# IOTLoRaSmartGreenhouseNode.net
KiCad netlist of a schematic drawn in Altium Designer
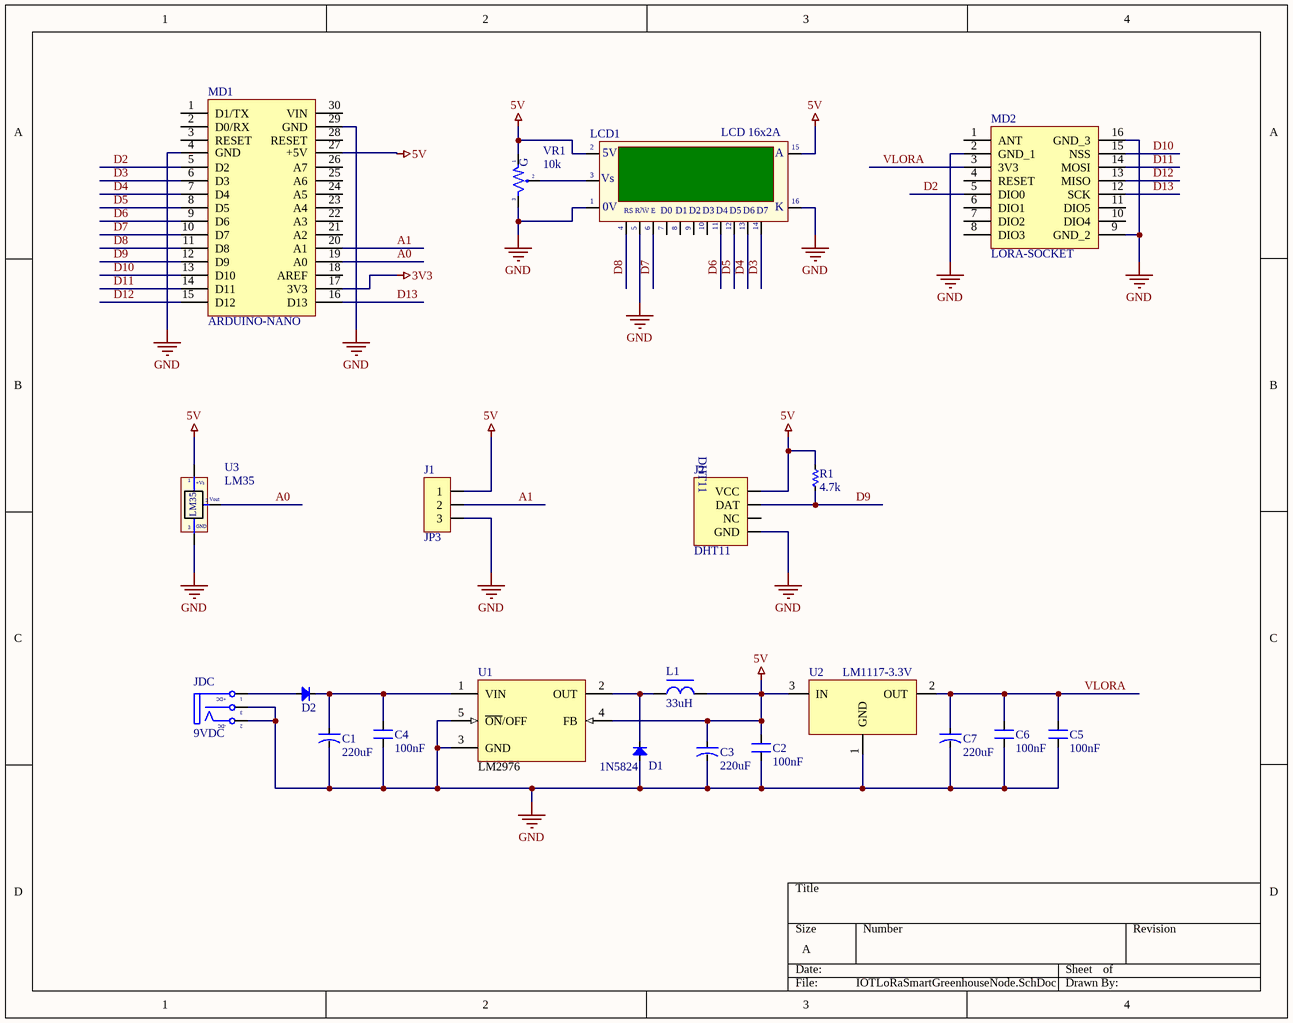
[diagram p0: IOTLoRaSmartGreenhouseNode.SchDoc]

(export (version "E")
  (design (tool "Eeschema 10.0.6"))
  (components
    (comp (ref "C1")
      (value "220uF")
      (footprint "CA-ALU-8")
      (description "Capacitor (Semiconductor SIM Model)")
      (fields (field (name "PUBLISHER") "Altium Limited"))
      (libsource (lib "LIBRARY") (part "CN-ALU-DIP"))
    )
    (comp (ref "C2") (value "100nF") (footprint "CN1.5") (libsource (lib "LIBRARY") (part "CN")))
    (comp (ref "C3")
      (value "220uF")
      (footprint "CA-ALU-8")
      (description "Capacitor (Semiconductor SIM Model)")
      (fields (field (name "PUBLISHER") "Altium Limited"))
      (libsource (lib "LIBRARY") (part "CN-ALU-DIP"))
    )
    (comp (ref "C4") (value "100nF") (footprint "CN1.5") (libsource (lib "LIBRARY") (part "CN")))
    (comp (ref "C5") (value "100nF") (footprint "CN1.5") (libsource (lib "LIBRARY") (part "CN")))
    (comp (ref "C6") (value "100nF") (footprint "CN1.5") (libsource (lib "LIBRARY") (part "CN")))
    (comp (ref "C7")
      (value "220uF")
      (footprint "CA-ALU-8")
      (description "Capacitor (Semiconductor SIM Model)")
      (fields (field (name "PUBLISHER") "Altium Limited"))
      (libsource (lib "LIBRARY") (part "CN-ALU-DIP"))
    )
    (comp (ref "D1")
      (value "1N5824")
      (footprint "DIO-5A")
      (description "Default Diode")
      (fields (field (name "PUBLISHER") "Altium Limited"))
      (libsource (lib "LIBRARY") (part "Diode"))
    )
    (comp (ref "D2")
      (value "Diode")
      (footprint "DIO-3A")
      (description "Default Diode")
      (fields (field (name "PUBLISHER") "Altium Limited"))
      (libsource (lib "LIBRARY") (part "Diode"))
    )
    (comp (ref "J1")
      (value "JP3")
      (footprint "JP3-D1C")
      (description "WR-PHD 2.54 mm Angled Socket Header")
      (fields
        (field (name "MANUFACTURER") "Würth Elektronik eiSos GmbH")
        (field (name "PARTNO") "613003143121")
        (field (name "CREATED BY") "Karrer Zheng")
      )
      (libsource (lib "LIBRARY") (part "JP3"))
    )
    (comp (ref "J2")
      (value "DHT11")
      (footprint "JP4-C1T")
      (fields
        (field (name "MANUFACTURER") "Würth Elektronik eiSos GmbH")
        (field (name "PARTNO") "613004143121")
        (field (name "CREATED BY") "Karrer Zheng")
      )
      (libsource (lib "LIBRARY") (part "DHT11"))
    )
    (comp (ref "JDC")
      (value "9VDC")
      (footprint "DC0")
      (description "Jac DC input")
      (libsource (lib "LIBRARY") (part "DCIN"))
    )
    (comp (ref "L1")
      (value "33uH")
      (footprint "L-DIP-M-10")
      (description "Inductor")
      (libsource (lib "LIBRARY") (part "L-DIP-1"))
    )
    (comp (ref "LCD1")
      (value "LCD 16x2A")
      (footprint "LCD16X2N")
      (description "LCD dipslay 16 char, 2 line")
      (libsource (lib "LIBRARY") (part "LCD16x2A"))
    )
    (comp (ref "MD1")
      (value "ARDUINO-NANO")
      (footprint "ARDUINO-NANO")
      (description "KIT Arduino Nano")
      (libsource (lib "phatvu1294_Lib") (part "ARDUINO-NANO"))
    )
    (comp (ref "MD2")
      (value "LORA-SOCKET")
      (footprint "LORA-SOCKET")
      (description "Socket LoRa RA01 va RA02")
      (libsource (lib "User") (part "LORA-SOCKET"))
    )
    (comp (ref "R1")
      (value "4.7k")
      (footprint "RES-1/4W")
      (description "Res")
      (fields
        (field (name "MANUFACTURER") "Generic Components")
        (field (name "PUBLISHER") "Altium Hobart Technology Centre")
      )
      (libsource (lib "LIBRARY") (part "Res"))
    )
    (comp (ref "U1") (value "LM2976") (footprint "TO263") (libsource (lib "LIBRARY") (part "LM2596")))
    (comp (ref "U2")
      (value "LM1117-3.3V")
      (footprint "SOT223")
      (description "800mA Low-Dropout Linear Regulator")
      (fields (field (name "CREATOR") "Nguyen Ba Bien"))
      (libsource (lib "LIBRARY") (part "LM1117"))
    )
    (comp (ref "U3")
      (value "LM35")
      (footprint "TO92-123")
      (description "Teminal")
      (libsource (lib "LIBRARY") (part "LM35"))
    )
    (comp (ref "VR1")
      (value "10k")
      (footprint "VR-S2")
      (description "Var Resistor")
      (libsource (lib "LIBRARY") (part "VR-S"))
    )
  )
  (nets
    (net (code "1") (name "/A0") (class "Default")
      (node (ref "MD1") (pin "19") (pinfunction "A0_19") (pintype "passive"))
      (node (ref "U3") (pin "2") (pinfunction "Vout_2") (pintype "passive"))
    )
    (net (code "2") (name "/A1") (class "Default")
      (node (ref "J1") (pin "2") (pinfunction "2_2") (pintype "passive"))
      (node (ref "MD1") (pin "20") (pinfunction "A1_20") (pintype "passive"))
    )
    (net (code "3") (name "/D2") (class "Default")
      (node (ref "MD1") (pin "5") (pinfunction "D2_5") (pintype "passive"))
      (node (ref "MD2") (pin "5") (pinfunction "DIO0_5") (pintype "passive"))
    )
    (net (code "4") (name "/D3") (class "Default")
      (node (ref "LCD1") (pin "14") (pinfunction "D7_14") (pintype "passive"))
      (node (ref "MD1") (pin "6") (pinfunction "D3_6") (pintype "passive"))
    )
    (net (code "5") (name "/D4") (class "Default")
      (node (ref "LCD1") (pin "13") (pinfunction "D6_13") (pintype "passive"))
      (node (ref "MD1") (pin "7") (pinfunction "D4_7") (pintype "passive"))
    )
    (net (code "6") (name "/D5") (class "Default")
      (node (ref "LCD1") (pin "12") (pinfunction "D5_12") (pintype "passive"))
      (node (ref "MD1") (pin "8") (pinfunction "D5_8") (pintype "passive"))
    )
    (net (code "7") (name "/D6") (class "Default")
      (node (ref "LCD1") (pin "11") (pinfunction "D4_11") (pintype "passive"))
      (node (ref "MD1") (pin "9") (pinfunction "D6_9") (pintype "passive"))
    )
    (net (code "8") (name "/D7") (class "Default")
      (node (ref "LCD1") (pin "6") (pinfunction "~{EN}_6") (pintype "passive"))
      (node (ref "MD1") (pin "10") (pinfunction "D7_10") (pintype "passive"))
    )
    (net (code "9") (name "/D8") (class "Default")
      (node (ref "LCD1") (pin "4") (pinfunction "RS_4") (pintype "passive"))
      (node (ref "MD1") (pin "11") (pinfunction "D8_11") (pintype "passive"))
    )
    (net (code "10") (name "/D9") (class "Default")
      (node (ref "J2") (pin "2") (pinfunction "DAT_2") (pintype "passive"))
      (node (ref "MD1") (pin "12") (pinfunction "D9_12") (pintype "passive"))
      (node (ref "R1") (pin "2") (pinfunction "2_2") (pintype "passive"))
    )
    (net (code "11") (name "/D10") (class "Default")
      (node (ref "MD1") (pin "13") (pinfunction "D10_13") (pintype "passive"))
      (node (ref "MD2") (pin "15") (pinfunction "NSS_15") (pintype "passive"))
    )
    (net (code "12") (name "/D11") (class "Default")
      (node (ref "MD1") (pin "14") (pinfunction "D11_14") (pintype "passive"))
      (node (ref "MD2") (pin "14") (pinfunction "MOSI_14") (pintype "passive"))
    )
    (net (code "13") (name "/D12") (class "Default")
      (node (ref "MD1") (pin "15") (pinfunction "D12_15") (pintype "passive"))
      (node (ref "MD2") (pin "13") (pinfunction "MISO_13") (pintype "passive"))
    )
    (net (code "14") (name "/D13") (class "Default")
      (node (ref "MD1") (pin "16") (pinfunction "D13_16") (pintype "passive"))
      (node (ref "MD2") (pin "12") (pinfunction "SCK_12") (pintype "passive"))
    )
    (net (code "15") (name "/VLORA") (class "Default")
      (node (ref "C5") (pin "1") (pinfunction "1_1") (pintype "passive"))
      (node (ref "C6") (pin "1") (pinfunction "1_1") (pintype "passive"))
      (node (ref "C7") (pin "1") (pinfunction "1_1") (pintype "passive"))
      (node (ref "MD2") (pin "3") (pinfunction "3V3_3") (pintype "passive"))
      (node (ref "U2") (pin "2") (pinfunction "OUT_2") (pintype "passive"))
    )
    (net (code "16") (name "3V3") (class "Default")
      (node (ref "MD1") (pin "17") (pinfunction "3V3_17") (pintype "passive"))
    )
    (net (code "17") (name "5V") (class "Default")
      (node (ref "C2") (pin "1") (pinfunction "1_1") (pintype "passive"))
      (node (ref "C3") (pin "1") (pinfunction "1_1") (pintype "passive"))
      (node (ref "J1") (pin "1") (pinfunction "1_1") (pintype "passive"))
      (node (ref "J2") (pin "1") (pinfunction "VCC_1") (pintype "passive"))
      (node (ref "L1") (pin "2") (pinfunction "2_2") (pintype "passive"))
      (node (ref "LCD1") (pin "15") (pinfunction "A_15") (pintype "passive"))
      (node (ref "LCD1") (pin "2") (pinfunction "VDD_2") (pintype "passive"))
      (node (ref "MD1") (pin "27") (pinfunction "+5V_27") (pintype "passive"))
      (node (ref "R1") (pin "1") (pinfunction "1_1") (pintype "passive"))
      (node (ref "U1") (pin "4") (pinfunction "FB_4") (pintype "input"))
      (node (ref "U2") (pin "3") (pinfunction "IN_3") (pintype "passive"))
      (node (ref "U3") (pin "1") (pinfunction "+Vs_1") (pintype "passive"))
      (node (ref "VR1") (pin "1") (pinfunction "1_1") (pintype "passive"))
    )
    (net (code "18") (name "GND") (class "Default")
      (node (ref "C1") (pin "2") (pinfunction "2_2") (pintype "passive"))
      (node (ref "C2") (pin "2") (pinfunction "2_2") (pintype "passive"))
      (node (ref "C3") (pin "2") (pinfunction "2_2") (pintype "passive"))
      (node (ref "C4") (pin "2") (pinfunction "2_2") (pintype "passive"))
      (node (ref "C5") (pin "2") (pinfunction "2_2") (pintype "passive"))
      (node (ref "C6") (pin "2") (pinfunction "2_2") (pintype "passive"))
      (node (ref "C7") (pin "2") (pinfunction "2_2") (pintype "passive"))
      (node (ref "D1") (pin "1") (pinfunction "A_1") (pintype "passive"))
      (node (ref "J1") (pin "3") (pinfunction "3_3") (pintype "passive"))
      (node (ref "J2") (pin "4") (pinfunction "GND_4") (pintype "passive"))
      (node (ref "JDC") (pin "2") (pinfunction "TN_2") (pintype "passive"))
      (node (ref "JDC") (pin "3") (pinfunction "S_3") (pintype "power_in"))
      (node (ref "LCD1") (pin "1") (pinfunction "GND_1") (pintype "passive"))
      (node (ref "LCD1") (pin "16") (pinfunction "K_16") (pintype "passive"))
      (node (ref "LCD1") (pin "5") (pinfunction "R/~{W}_5") (pintype "passive"))
      (node (ref "MD1") (pin "29") (pinfunction "GND_29") (pintype "passive"))
      (node (ref "MD1") (pin "4") (pinfunction "GND_4") (pintype "passive"))
      (node (ref "MD2") (pin "16") (pinfunction "GND_3_16") (pintype "passive"))
      (node (ref "MD2") (pin "2") (pinfunction "GND_1_2") (pintype "passive"))
      (node (ref "MD2") (pin "9") (pinfunction "GND_2_9") (pintype "passive"))
      (node (ref "U1") (pin "3") (pinfunction "GND_3") (pintype "power_in"))
      (node (ref "U1") (pin "5") (pinfunction "~{ON}/OFF_5") (pintype "input"))
      (node (ref "U2") (pin "1") (pinfunction "GND_1") (pintype "passive"))
      (node (ref "U3") (pin "3") (pinfunction "-_3") (pintype "passive"))
      (node (ref "VR1") (pin "3") (pinfunction "3_3") (pintype "passive"))
    )
    (net (code "19") (name "Net-(D1-K)") (class "Default")
      (node (ref "D1") (pin "2") (pinfunction "K_2") (pintype "passive"))
      (node (ref "L1") (pin "1") (pinfunction "1_1") (pintype "passive"))
      (node (ref "U1") (pin "2") (pinfunction "OUT_2") (pintype "power_in"))
    )
    (net (code "20") (name "Net-(D2-A)") (class "Default")
      (node (ref "D2") (pin "1") (pinfunction "A_1") (pintype "passive"))
      (node (ref "JDC") (pin "1") (pinfunction "T_1") (pintype "passive"))
    )
    (net (code "21") (name "Net-(D2-K)") (class "Default")
      (node (ref "C1") (pin "1") (pinfunction "1_1") (pintype "passive"))
      (node (ref "C4") (pin "1") (pinfunction "1_1") (pintype "passive"))
      (node (ref "D2") (pin "2") (pinfunction "K_2") (pintype "passive"))
      (node (ref "U1") (pin "1") (pinfunction "VIN_1") (pintype "power_in"))
    )
    (net (code "22") (name "Net-(LCD1-VEE)") (class "Default")
      (node (ref "LCD1") (pin "3") (pinfunction "VEE_3") (pintype "passive"))
      (node (ref "VR1") (pin "2") (pinfunction "2_2") (pintype "passive"))
    )
    (net (code "23") (name "unconnected-(J2-NC-Pad3)") (class "Default")
      (node (ref "J2") (pin "3") (pinfunction "NC_3") (pintype "passive"))
    )
    (net (code "24") (name "unconnected-(LCD1-D0-Pad7)") (class "Default")
      (node (ref "LCD1") (pin "7") (pinfunction "D0_7") (pintype "passive"))
    )
    (net (code "25") (name "unconnected-(LCD1-D1-Pad8)") (class "Default")
      (node (ref "LCD1") (pin "8") (pinfunction "D1_8") (pintype "passive"))
    )
    (net (code "26") (name "unconnected-(LCD1-D2-Pad9)") (class "Default")
      (node (ref "LCD1") (pin "9") (pinfunction "D2_9") (pintype "passive"))
    )
    (net (code "27") (name "unconnected-(LCD1-D3-Pad10)") (class "Default")
      (node (ref "LCD1") (pin "10") (pinfunction "D3_10") (pintype "passive"))
    )
    (net (code "28") (name "unconnected-(MD1-A2-Pad21)") (class "Default")
      (node (ref "MD1") (pin "21") (pinfunction "A2_21") (pintype "passive"))
    )
    (net (code "29") (name "unconnected-(MD1-A3-Pad22)") (class "Default")
      (node (ref "MD1") (pin "22") (pinfunction "A3_22") (pintype "passive"))
    )
    (net (code "30") (name "unconnected-(MD1-A4-Pad23)") (class "Default")
      (node (ref "MD1") (pin "23") (pinfunction "A4_23") (pintype "passive"))
    )
    (net (code "31") (name "unconnected-(MD1-A5-Pad24)") (class "Default")
      (node (ref "MD1") (pin "24") (pinfunction "A5_24") (pintype "passive"))
    )
    (net (code "32") (name "unconnected-(MD1-A6-Pad25)") (class "Default")
      (node (ref "MD1") (pin "25") (pinfunction "A6_25") (pintype "passive"))
    )
    (net (code "33") (name "unconnected-(MD1-A7-Pad26)") (class "Default")
      (node (ref "MD1") (pin "26") (pinfunction "A7_26") (pintype "passive"))
    )
    (net (code "34") (name "unconnected-(MD1-AREF-Pad18)") (class "Default")
      (node (ref "MD1") (pin "18") (pinfunction "AREF_18") (pintype "passive"))
    )
    (net (code "35") (name "unconnected-(MD1-D0{slash}RX-Pad2)") (class "Default")
      (node (ref "MD1") (pin "2") (pinfunction "D0/RX_2") (pintype "passive"))
    )
    (net (code "36") (name "unconnected-(MD1-D1{slash}TX-Pad1)") (class "Default")
      (node (ref "MD1") (pin "1") (pinfunction "D1/TX_1") (pintype "passive"))
    )
    (net (code "37") (name "unconnected-(MD1-RESET-Pad3)") (class "Default")
      (node (ref "MD1") (pin "3") (pinfunction "RESET_3") (pintype "passive"))
    )
    (net (code "38") (name "unconnected-(MD1-RESET-Pad28)") (class "Default")
      (node (ref "MD1") (pin "28") (pinfunction "RESET_28") (pintype "passive"))
    )
    (net (code "39") (name "unconnected-(MD1-VIN-Pad30)") (class "Default")
      (node (ref "MD1") (pin "30") (pinfunction "VIN_30") (pintype "passive"))
    )
    (net (code "40") (name "unconnected-(MD2-ANT-Pad1)") (class "Default")
      (node (ref "MD2") (pin "1") (pinfunction "ANT_1") (pintype "passive"))
    )
    (net (code "41") (name "unconnected-(MD2-DIO1-Pad6)") (class "Default")
      (node (ref "MD2") (pin "6") (pinfunction "DIO1_6") (pintype "passive"))
    )
    (net (code "42") (name "unconnected-(MD2-DIO2-Pad7)") (class "Default")
      (node (ref "MD2") (pin "7") (pinfunction "DIO2_7") (pintype "passive"))
    )
    (net (code "43") (name "unconnected-(MD2-DIO3-Pad8)") (class "Default")
      (node (ref "MD2") (pin "8") (pinfunction "DIO3_8") (pintype "passive"))
    )
    (net (code "44") (name "unconnected-(MD2-DIO4-Pad10)") (class "Default")
      (node (ref "MD2") (pin "10") (pinfunction "DIO4_10") (pintype "passive"))
    )
    (net (code "45") (name "unconnected-(MD2-DIO5-Pad11)") (class "Default")
      (node (ref "MD2") (pin "11") (pinfunction "DIO5_11") (pintype "passive"))
    )
    (net (code "46") (name "unconnected-(MD2-RESET-Pad4)") (class "Default")
      (node (ref "MD2") (pin "4") (pinfunction "RESET_4") (pintype "passive"))
    )
  )
)
